# gflexgostack.net
KiCad netlist of a schematic drawn in EAGLE
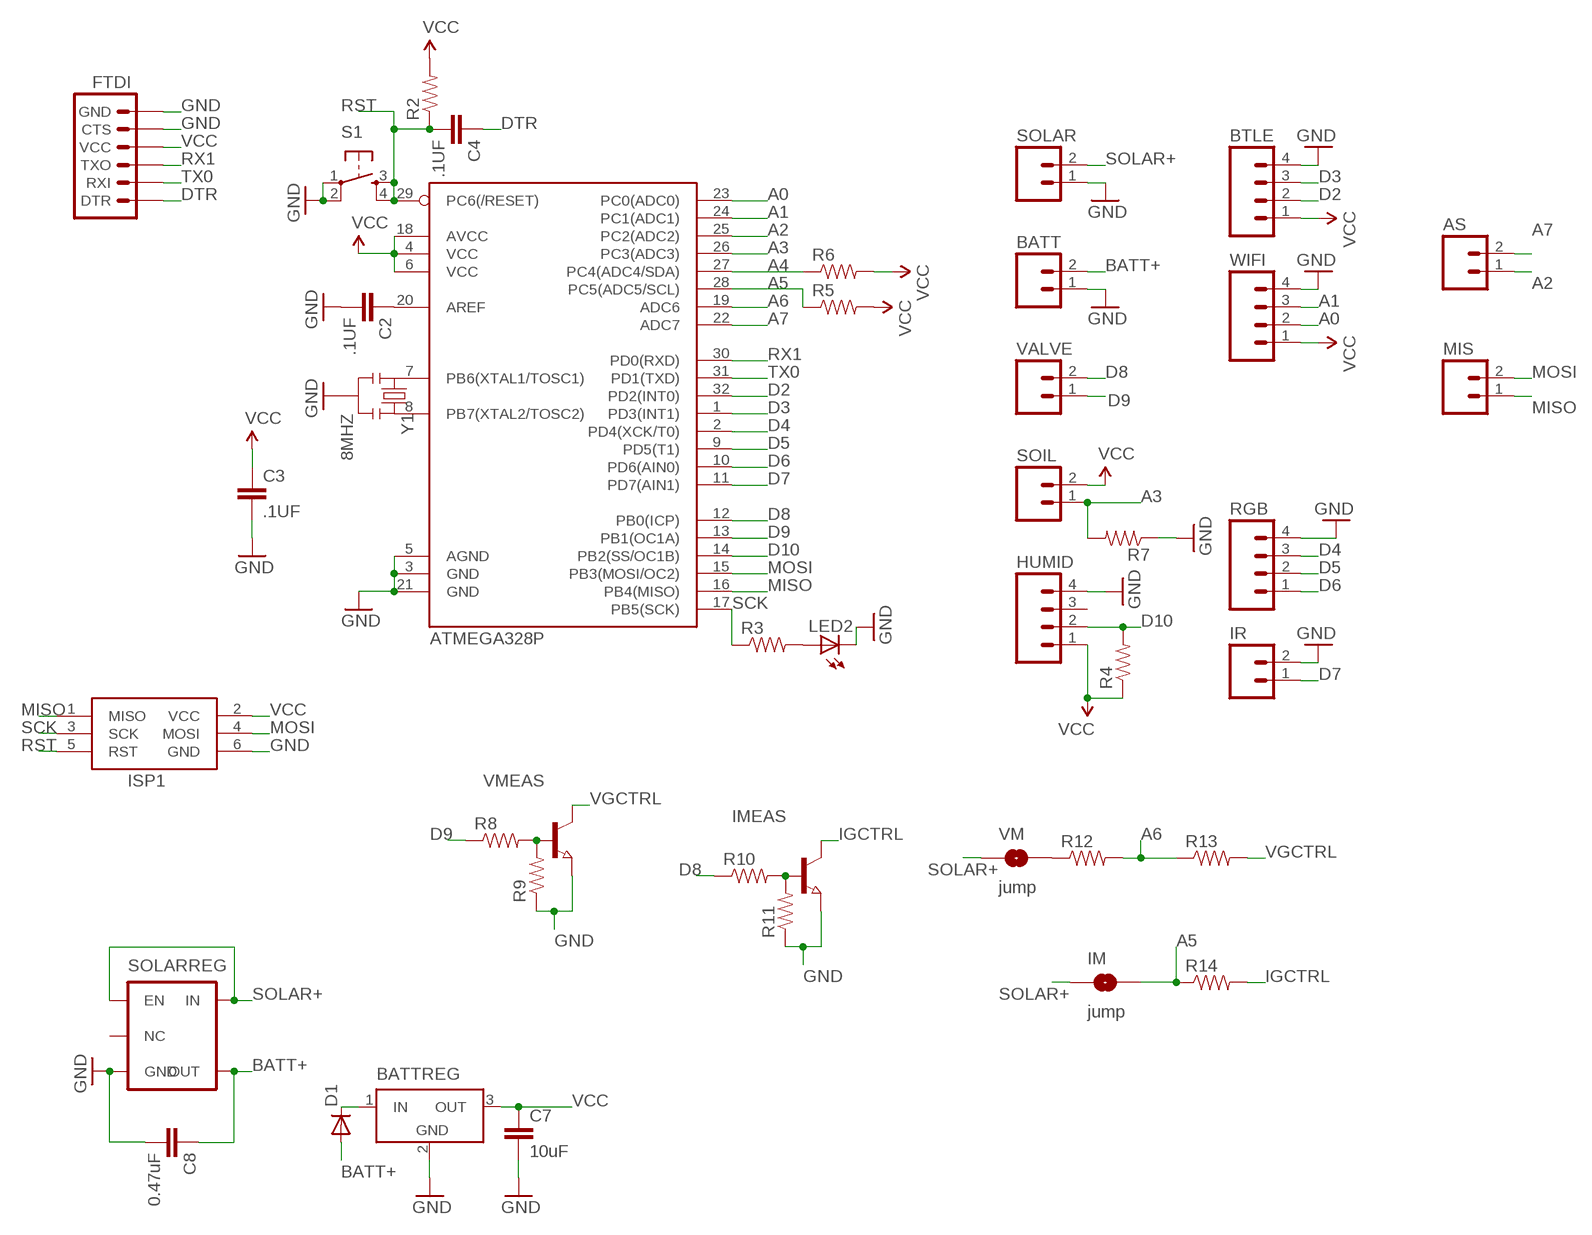
[diagram p0: schematic, sheet 1]

(export (version "E")
  (design (tool "Eeschema 10.0.6"))
  (components
    (comp (ref "AS")
      (value "M02PTH")
      (footprint "eagle-import:1X02")
      (libsource (lib "eagle-import") (part "M02PTH"))
    )
    (comp (ref "ATMEGA328P")
      (value "ATMEGA168")
      (footprint "eagle-import:TQFP32-08")
      (libsource (lib "eagle-import") (part "ATMEGA168"))
    )
    (comp (ref "BATT")
      (value "M02PTH")
      (footprint "eagle-import:1X02")
      (libsource (lib "eagle-import") (part "M02PTH"))
    )
    (comp (ref "BATTREG")
      (value "LT1129CST5")
      (footprint "eagle-import:SOT223")
      (fields (field (name "MPN") "LT1129CST-5#PBF") (field (name "MPN_1") "LT1129CST-3.3#PBF-ND"))
      (libsource (lib "eagle-import") (part "LT1129CST5"))
    )
    (comp (ref "BTLE")
      (value "M04PTH")
      (footprint "eagle-import:1X04")
      (libsource (lib "eagle-import") (part "M04PTH"))
    )
    (comp (ref "C2")
      (value ".1UF")
      (footprint "eagle-import:0402-CAP")
      (libsource (lib "eagle-import") (part ".1UF-CER"))
    )
    (comp (ref "C3")
      (value ".1UF")
      (footprint "eagle-import:0402-CAP")
      (libsource (lib "eagle-import") (part ".1UF-CER"))
    )
    (comp (ref "C4")
      (value ".1UF")
      (footprint "eagle-import:0402-CAP")
      (libsource (lib "eagle-import") (part ".1UF-CER"))
    )
    (comp (ref "C7")
      (value "10uF")
      (footprint "eagle-import:0402-CAP")
      (libsource (lib "eagle-import") (part ".1UF-CER"))
    )
    (comp (ref "C8")
      (value "0.47uF")
      (footprint "eagle-import:0402-CAP")
      (libsource (lib "eagle-import") (part ".1UF-CER"))
    )
    (comp (ref "D1")
      (value "DIODESMA")
      (footprint "eagle-import:SMA-DIODE")
      (libsource (lib "eagle-import") (part "DIODESMA"))
    )
    (comp (ref "FTDI")
      (value "ARDUINO_SERIAL_PROGRAMPTH")
      (footprint "eagle-import:1X06")
      (libsource (lib "eagle-import") (part "ARDUINO_SERIAL_PROGRAMPTH"))
    )
    (comp (ref "HUMID")
      (value "M04PTH")
      (footprint "eagle-import:1X04")
      (libsource (lib "eagle-import") (part "M04PTH"))
    )
    (comp (ref "IM")
      (value "jump")
      (footprint "eagle-import:SJ_2S-TRACE")
      (libsource (lib "eagle-import") (part "SOLDERJUMPERTRACE"))
    )
    (comp (ref "IMEAS")
      (value "NPN-TRANSISTOR_SOT23")
      (footprint "eagle-import:SOT23")
      (libsource (lib "eagle-import") (part "NPN-TRANSISTOR_SOT23"))
    )
    (comp (ref "IR")
      (value "M02PTH")
      (footprint "eagle-import:1X02")
      (libsource (lib "eagle-import") (part "M02PTH"))
    )
    (comp (ref "ISP1")
      (value "AVRISP-6")
      (footprint "eagle-import:AVRISP")
      (libsource (lib "eagle-import") (part "AVRISP-6"))
    )
    (comp (ref "LED2")
      (value "LED0603")
      (footprint "eagle-import:LED-0603")
      (libsource (lib "eagle-import") (part "LED0603"))
    )
    (comp (ref "MIS")
      (value "M02PTH")
      (footprint "eagle-import:1X02")
      (libsource (lib "eagle-import") (part "M02PTH"))
    )
    (comp (ref "R2")
      (value "RESISTOR0603-RES")
      (footprint "eagle-import:0603-RES")
      (libsource (lib "eagle-import") (part "RESISTOR0603-RES"))
    )
    (comp (ref "R3")
      (value "RESISTOR0603-RES")
      (footprint "eagle-import:0603-RES")
      (libsource (lib "eagle-import") (part "RESISTOR0603-RES"))
    )
    (comp (ref "R4")
      (value "RESISTOR0603-RES")
      (footprint "eagle-import:0603-RES")
      (libsource (lib "eagle-import") (part "RESISTOR0603-RES"))
    )
    (comp (ref "R5")
      (value "RESISTOR0603-RES")
      (footprint "eagle-import:0603-RES")
      (libsource (lib "eagle-import") (part "RESISTOR0603-RES"))
    )
    (comp (ref "R6")
      (value "RESISTOR0603-RES")
      (footprint "eagle-import:0603-RES")
      (libsource (lib "eagle-import") (part "RESISTOR0603-RES"))
    )
    (comp (ref "R7")
      (value "RESISTOR0603-RES")
      (footprint "eagle-import:0603-RES")
      (libsource (lib "eagle-import") (part "RESISTOR0603-RES"))
    )
    (comp (ref "R8")
      (value "RESISTOR0603-RES")
      (footprint "eagle-import:0603-RES")
      (libsource (lib "eagle-import") (part "RESISTOR0603-RES"))
    )
    (comp (ref "R9")
      (value "RESISTOR0603-RES")
      (footprint "eagle-import:0603-RES")
      (libsource (lib "eagle-import") (part "RESISTOR0603-RES"))
    )
    (comp (ref "R10")
      (value "RESISTOR0603-RES")
      (footprint "eagle-import:0603-RES")
      (libsource (lib "eagle-import") (part "RESISTOR0603-RES"))
    )
    (comp (ref "R11")
      (value "RESISTOR0603-RES")
      (footprint "eagle-import:0603-RES")
      (libsource (lib "eagle-import") (part "RESISTOR0603-RES"))
    )
    (comp (ref "R12")
      (value "RESISTOR0603-RES")
      (footprint "eagle-import:0603-RES")
      (libsource (lib "eagle-import") (part "RESISTOR0603-RES"))
    )
    (comp (ref "R13")
      (value "RESISTOR0603-RES")
      (footprint "eagle-import:0603-RES")
      (libsource (lib "eagle-import") (part "RESISTOR0603-RES"))
    )
    (comp (ref "R14")
      (value "RESISTOR0603-RES")
      (footprint "eagle-import:0603-RES")
      (libsource (lib "eagle-import") (part "RESISTOR0603-RES"))
    )
    (comp (ref "RGB")
      (value "M04PTH")
      (footprint "eagle-import:1X04")
      (libsource (lib "eagle-import") (part "M04PTH"))
    )
    (comp (ref "S1")
      (value "TAC_SWITCHSMD")
      (footprint "eagle-import:TACTILE_SWITCH_SMD")
      (libsource (lib "eagle-import") (part "TAC_SWITCHSMD"))
    )
    (comp (ref "SOIL")
      (value "M02PTH")
      (footprint "eagle-import:1X02")
      (libsource (lib "eagle-import") (part "M02PTH"))
    )
    (comp (ref "SOLAR")
      (value "M02PTH")
      (footprint "eagle-import:1X02")
      (libsource (lib "eagle-import") (part "M02PTH"))
    )
    (comp (ref "SOLARREG")
      (value "V_REG_MIC52195V")
      (footprint "eagle-import:SOT23-5")
      (libsource (lib "eagle-import") (part "V_REG_MIC52195V"))
    )
    (comp (ref "VALVE")
      (value "M02PTH")
      (footprint "eagle-import:1X02")
      (libsource (lib "eagle-import") (part "M02PTH"))
    )
    (comp (ref "VM")
      (value "jump")
      (footprint "eagle-import:SJ_2S-TRACE")
      (libsource (lib "eagle-import") (part "SOLDERJUMPERTRACE"))
    )
    (comp (ref "VMEAS")
      (value "NPN-TRANSISTOR_SOT23")
      (footprint "eagle-import:SOT23")
      (libsource (lib "eagle-import") (part "NPN-TRANSISTOR_SOT23"))
    )
    (comp (ref "WIFI")
      (value "M04PTH")
      (footprint "eagle-import:1X04")
      (libsource (lib "eagle-import") (part "M04PTH"))
    )
    (comp (ref "Y1")
      (value "8MHZ")
      (footprint "eagle-import:RESONATOR-SMD")
      (libsource (lib "eagle-import") (part "RESONATOR8MHZ"))
    )
  )
  (nets
    (net (code "1") (name "/A0") (class "Default")
      (node (ref "ATMEGA328P") (pin "23") (pinfunction "PC0(ADC0)_23") (pintype "bidirectional"))
      (node (ref "WIFI") (pin "2") (pinfunction "2_2") (pintype "passive"))
    )
    (net (code "2") (name "/A1") (class "Default")
      (node (ref "ATMEGA328P") (pin "24") (pinfunction "PC1(ADC1)_24") (pintype "bidirectional"))
      (node (ref "WIFI") (pin "3") (pinfunction "3_3") (pintype "passive"))
    )
    (net (code "3") (name "/A2") (class "Default")
      (node (ref "AS") (pin "1") (pinfunction "1_1") (pintype "passive"))
      (node (ref "ATMEGA328P") (pin "25") (pinfunction "PC2(ADC2)_25") (pintype "bidirectional"))
    )
    (net (code "4") (name "/A3") (class "Default")
      (node (ref "ATMEGA328P") (pin "26") (pinfunction "PC3(ADC3)_26") (pintype "bidirectional"))
      (node (ref "R7") (pin "2") (pinfunction "2_2") (pintype "passive"))
      (node (ref "SOIL") (pin "1") (pinfunction "1_1") (pintype "passive"))
    )
    (net (code "5") (name "/A4") (class "Default")
      (node (ref "ATMEGA328P") (pin "27") (pinfunction "PC4(ADC4/SDA)_27") (pintype "bidirectional"))
      (node (ref "R6") (pin "1") (pinfunction "1_1") (pintype "passive"))
    )
    (net (code "6") (name "/A5") (class "Default")
      (node (ref "ATMEGA328P") (pin "28") (pinfunction "PC5(ADC5/SCL)_28") (pintype "bidirectional"))
      (node (ref "IM") (pin "2") (pinfunction "2_2") (pintype "passive"))
      (node (ref "R14") (pin "1") (pinfunction "1_1") (pintype "passive"))
      (node (ref "R5") (pin "1") (pinfunction "1_1") (pintype "passive"))
    )
    (net (code "7") (name "/A6") (class "Default")
      (node (ref "ATMEGA328P") (pin "19") (pinfunction "ADC6_19") (pintype "bidirectional"))
      (node (ref "R12") (pin "2") (pinfunction "2_2") (pintype "passive"))
      (node (ref "R13") (pin "1") (pinfunction "1_1") (pintype "passive"))
    )
    (net (code "8") (name "/A7") (class "Default")
      (node (ref "AS") (pin "2") (pinfunction "2_2") (pintype "passive"))
      (node (ref "ATMEGA328P") (pin "22") (pinfunction "ADC7_22") (pintype "bidirectional"))
    )
    (net (code "9") (name "/BATT+") (class "Default")
      (node (ref "BATT") (pin "2") (pinfunction "2_2") (pintype "passive"))
      (node (ref "C8") (pin "1") (pinfunction "1_1") (pintype "passive"))
      (node (ref "D1") (pin "A") (pinfunction "A_A") (pintype "passive"))
      (node (ref "SOLARREG") (pin "4") (pinfunction "OUT_4") (pintype "input"))
    )
    (net (code "10") (name "/D2") (class "Default")
      (node (ref "ATMEGA328P") (pin "32") (pinfunction "PD2(INT0)_32") (pintype "bidirectional"))
      (node (ref "BTLE") (pin "2") (pinfunction "2_2") (pintype "passive"))
    )
    (net (code "11") (name "/D3") (class "Default")
      (node (ref "ATMEGA328P") (pin "1") (pinfunction "PD3(INT1)_1") (pintype "bidirectional"))
      (node (ref "BTLE") (pin "3") (pinfunction "3_3") (pintype "passive"))
    )
    (net (code "12") (name "/D4") (class "Default")
      (node (ref "ATMEGA328P") (pin "2") (pinfunction "PD4(XCK/T0)_2") (pintype "bidirectional"))
      (node (ref "RGB") (pin "3") (pinfunction "3_3") (pintype "passive"))
    )
    (net (code "13") (name "/D5") (class "Default")
      (node (ref "ATMEGA328P") (pin "9") (pinfunction "PD5(T1)_9") (pintype "bidirectional"))
      (node (ref "RGB") (pin "2") (pinfunction "2_2") (pintype "passive"))
    )
    (net (code "14") (name "/D6") (class "Default")
      (node (ref "ATMEGA328P") (pin "10") (pinfunction "PD6(AIN0)_10") (pintype "bidirectional"))
      (node (ref "RGB") (pin "1") (pinfunction "1_1") (pintype "passive"))
    )
    (net (code "15") (name "/D7") (class "Default")
      (node (ref "ATMEGA328P") (pin "11") (pinfunction "PD7(AIN1)_11") (pintype "bidirectional"))
      (node (ref "IR") (pin "1") (pinfunction "1_1") (pintype "passive"))
    )
    (net (code "16") (name "/D8") (class "Default")
      (node (ref "ATMEGA328P") (pin "12") (pinfunction "PB0(ICP)_12") (pintype "bidirectional"))
      (node (ref "R10") (pin "1") (pinfunction "1_1") (pintype "passive"))
      (node (ref "VALVE") (pin "2") (pinfunction "2_2") (pintype "passive"))
    )
    (net (code "17") (name "/D9") (class "Default")
      (node (ref "ATMEGA328P") (pin "13") (pinfunction "PB1(OC1A)_13") (pintype "bidirectional"))
      (node (ref "R8") (pin "1") (pinfunction "1_1") (pintype "passive"))
      (node (ref "VALVE") (pin "1") (pinfunction "1_1") (pintype "passive"))
    )
    (net (code "18") (name "/D10") (class "Default")
      (node (ref "ATMEGA328P") (pin "14") (pinfunction "PB2(SS/OC1B)_14") (pintype "bidirectional"))
      (node (ref "HUMID") (pin "2") (pinfunction "2_2") (pintype "passive"))
      (node (ref "R4") (pin "2") (pinfunction "2_2") (pintype "passive"))
    )
    (net (code "19") (name "/DTR") (class "Default")
      (node (ref "C4") (pin "1") (pinfunction "1_1") (pintype "passive"))
      (node (ref "FTDI") (pin "1") (pinfunction "DTR_1") (pintype "passive"))
    )
    (net (code "20") (name "/IGCTRL") (class "Default")
      (node (ref "IMEAS") (pin "3") (pinfunction "C_3") (pintype "passive"))
      (node (ref "R14") (pin "2") (pinfunction "2_2") (pintype "passive"))
    )
    (net (code "21") (name "/MISO") (class "Default")
      (node (ref "ATMEGA328P") (pin "16") (pinfunction "PB4(MISO)_16") (pintype "bidirectional"))
      (node (ref "ISP1") (pin "1") (pinfunction "MISO_1") (pintype "input"))
      (node (ref "MIS") (pin "1") (pinfunction "1_1") (pintype "passive"))
    )
    (net (code "22") (name "/MOSI") (class "Default")
      (node (ref "ATMEGA328P") (pin "15") (pinfunction "PB3(MOSI/OC2)_15") (pintype "bidirectional"))
      (node (ref "ISP1") (pin "4") (pinfunction "MOSI_4") (pintype "output"))
      (node (ref "MIS") (pin "2") (pinfunction "2_2") (pintype "passive"))
    )
    (net (code "23") (name "/RST") (class "Default")
      (node (ref "ATMEGA328P") (pin "29") (pinfunction "PC6(/RESET)_29") (pintype "bidirectional"))
      (node (ref "C4") (pin "2") (pinfunction "2_2") (pintype "passive"))
      (node (ref "ISP1") (pin "5") (pinfunction "RST_5") (pintype "output"))
      (node (ref "R2") (pin "1") (pinfunction "1_1") (pintype "passive"))
      (node (ref "S1") (pin "3") (pinfunction "3_3") (pintype "passive"))
      (node (ref "S1") (pin "4") (pinfunction "4_4") (pintype "passive"))
    )
    (net (code "24") (name "/RX1") (class "Default")
      (node (ref "ATMEGA328P") (pin "30") (pinfunction "PD0(RXD)_30") (pintype "bidirectional"))
      (node (ref "FTDI") (pin "3") (pinfunction "TXO_3") (pintype "passive"))
    )
    (net (code "25") (name "/SCK") (class "Default")
      (node (ref "ATMEGA328P") (pin "17") (pinfunction "PB5(SCK)_17") (pintype "bidirectional"))
      (node (ref "ISP1") (pin "3") (pinfunction "SCK_3") (pintype "output"))
      (node (ref "R3") (pin "1") (pinfunction "1_1") (pintype "passive"))
    )
    (net (code "26") (name "/SOLAR+") (class "Default")
      (node (ref "IM") (pin "1") (pinfunction "1_1") (pintype "passive"))
      (node (ref "SOLAR") (pin "2") (pinfunction "2_2") (pintype "passive"))
      (node (ref "SOLARREG") (pin "1") (pinfunction "EN_1") (pintype "input"))
      (node (ref "SOLARREG") (pin "5") (pinfunction "IN_5") (pintype "passive"))
      (node (ref "VM") (pin "1") (pinfunction "1_1") (pintype "passive"))
    )
    (net (code "27") (name "/TX0") (class "Default")
      (node (ref "ATMEGA328P") (pin "31") (pinfunction "PD1(TXD)_31") (pintype "bidirectional"))
      (node (ref "FTDI") (pin "2") (pinfunction "RXI_2") (pintype "passive"))
    )
    (net (code "28") (name "/VGCTRL") (class "Default")
      (node (ref "R13") (pin "2") (pinfunction "2_2") (pintype "passive"))
      (node (ref "VMEAS") (pin "3") (pinfunction "C_3") (pintype "passive"))
    )
    (net (code "29") (name "GND") (class "Default")
      (node (ref "ATMEGA328P") (pin "21") (pinfunction "GND_21") (pintype "bidirectional"))
      (node (ref "ATMEGA328P") (pin "3") (pinfunction "GND_3") (pintype "bidirectional"))
      (node (ref "ATMEGA328P") (pin "5") (pinfunction "AGND_5") (pintype "bidirectional"))
      (node (ref "BATT") (pin "1") (pinfunction "1_1") (pintype "passive"))
      (node (ref "BATTREG") (pin "2") (pinfunction "GND_2") (pintype "power_in"))
      (node (ref "BTLE") (pin "4") (pinfunction "4_4") (pintype "passive"))
      (node (ref "C2") (pin "2") (pinfunction "2_2") (pintype "passive"))
      (node (ref "C3") (pin "2") (pinfunction "2_2") (pintype "passive"))
      (node (ref "C7") (pin "2") (pinfunction "2_2") (pintype "passive"))
      (node (ref "C8") (pin "2") (pinfunction "2_2") (pintype "passive"))
      (node (ref "FTDI") (pin "5") (pinfunction "CTS_5") (pintype "passive"))
      (node (ref "FTDI") (pin "6") (pinfunction "GND_6") (pintype "passive"))
      (node (ref "HUMID") (pin "4") (pinfunction "4_4") (pintype "passive"))
      (node (ref "IMEAS") (pin "2") (pinfunction "E_2") (pintype "passive"))
      (node (ref "IR") (pin "2") (pinfunction "2_2") (pintype "passive"))
      (node (ref "ISP1") (pin "6") (pinfunction "GND_6") (pintype "power_in"))
      (node (ref "LED2") (pin "C") (pinfunction "C_C") (pintype "passive"))
      (node (ref "R11") (pin "1") (pinfunction "1_1") (pintype "passive"))
      (node (ref "R7") (pin "1") (pinfunction "1_1") (pintype "passive"))
      (node (ref "R9") (pin "1") (pinfunction "1_1") (pintype "passive"))
      (node (ref "RGB") (pin "4") (pinfunction "4_4") (pintype "passive"))
      (node (ref "S1") (pin "1") (pinfunction "1_1") (pintype "passive"))
      (node (ref "S1") (pin "2") (pinfunction "2_2") (pintype "passive"))
      (node (ref "SOLAR") (pin "1") (pinfunction "1_1") (pintype "passive"))
      (node (ref "SOLARREG") (pin "3") (pinfunction "GND_3") (pintype "input"))
      (node (ref "VMEAS") (pin "2") (pinfunction "E_2") (pintype "passive"))
      (node (ref "WIFI") (pin "4") (pinfunction "4_4") (pintype "passive"))
      (node (ref "Y1") (pin "2") (pinfunction "2_2") (pintype "passive"))
    )
    (net (code "30") (name "Net-(ATMEGA328P-AREF)") (class "Default")
      (node (ref "ATMEGA328P") (pin "20") (pinfunction "AREF_20") (pintype "bidirectional"))
      (node (ref "C2") (pin "1") (pinfunction "1_1") (pintype "passive"))
    )
    (net (code "31") (name "Net-(ATMEGA328P-PB6(XTAL1{slash}TOSC1))") (class "Default")
      (node (ref "ATMEGA328P") (pin "7") (pinfunction "PB6(XTAL1/TOSC1)_7") (pintype "bidirectional"))
      (node (ref "Y1") (pin "1") (pinfunction "1_1") (pintype "passive"))
    )
    (net (code "32") (name "Net-(ATMEGA328P-PB7(XTAL2{slash}TOSC2))") (class "Default")
      (node (ref "ATMEGA328P") (pin "8") (pinfunction "PB7(XTAL2/TOSC2)_8") (pintype "bidirectional"))
      (node (ref "Y1") (pin "3") (pinfunction "3_3") (pintype "passive"))
    )
    (net (code "33") (name "Net-(BATTREGA-IN)") (class "Default")
      (node (ref "BATTREG") (pin "1") (pinfunction "IN_1") (pintype "input"))
      (node (ref "D1") (pin "C") (pinfunction "C_C") (pintype "passive"))
    )
    (net (code "34") (name "Net-(IMEAS-B)") (class "Default")
      (node (ref "IMEAS") (pin "1") (pinfunction "B_1") (pintype "passive"))
      (node (ref "R10") (pin "2") (pinfunction "2_2") (pintype "passive"))
      (node (ref "R11") (pin "2") (pinfunction "2_2") (pintype "passive"))
    )
    (net (code "35") (name "Net-(LED2-PadA)") (class "Default")
      (node (ref "LED2") (pin "A") (pinfunction "A_A") (pintype "passive"))
      (node (ref "R3") (pin "2") (pinfunction "2_2") (pintype "passive"))
    )
    (net (code "36") (name "Net-(R12-Pad1)") (class "Default")
      (node (ref "R12") (pin "1") (pinfunction "1_1") (pintype "passive"))
      (node (ref "VM") (pin "2") (pinfunction "2_2") (pintype "passive"))
    )
    (net (code "37") (name "Net-(VMEAS-B)") (class "Default")
      (node (ref "R8") (pin "2") (pinfunction "2_2") (pintype "passive"))
      (node (ref "R9") (pin "2") (pinfunction "2_2") (pintype "passive"))
      (node (ref "VMEAS") (pin "1") (pinfunction "B_1") (pintype "passive"))
    )
    (net (code "38") (name "VCC") (class "Default")
      (node (ref "ATMEGA328P") (pin "18") (pinfunction "AVCC_18") (pintype "bidirectional"))
      (node (ref "ATMEGA328P") (pin "4") (pinfunction "VCC_4") (pintype "bidirectional"))
      (node (ref "ATMEGA328P") (pin "6") (pinfunction "VCC_6") (pintype "bidirectional"))
      (node (ref "BATTREG") (pin "3") (pinfunction "OUT_3") (pintype "output"))
      (node (ref "BTLE") (pin "1") (pinfunction "1_1") (pintype "passive"))
      (node (ref "C3") (pin "1") (pinfunction "1_1") (pintype "passive"))
      (node (ref "C7") (pin "1") (pinfunction "1_1") (pintype "passive"))
      (node (ref "FTDI") (pin "4") (pinfunction "VCC_4") (pintype "passive"))
      (node (ref "HUMID") (pin "1") (pinfunction "1_1") (pintype "passive"))
      (node (ref "ISP1") (pin "2") (pinfunction "VCC_2") (pintype "power_in"))
      (node (ref "R2") (pin "2") (pinfunction "2_2") (pintype "passive"))
      (node (ref "R4") (pin "1") (pinfunction "1_1") (pintype "passive"))
      (node (ref "R5") (pin "2") (pinfunction "2_2") (pintype "passive"))
      (node (ref "R6") (pin "2") (pinfunction "2_2") (pintype "passive"))
      (node (ref "SOIL") (pin "2") (pinfunction "2_2") (pintype "passive"))
      (node (ref "WIFI") (pin "1") (pinfunction "1_1") (pintype "passive"))
    )
    (net (code "39") (name "unconnected-(HUMID-Pad3)") (class "Default")
      (node (ref "HUMID") (pin "3") (pinfunction "3_3") (pintype "passive"))
    )
    (net (code "40") (name "unconnected-(SOLARREG-NC-Pad2)") (class "Default")
      (node (ref "SOLARREG") (pin "2") (pinfunction "NC_2") (pintype "input"))
    )
  )
)
